# MIPI_To_HDMI.net
KiCad netlist of a schematic drawn in Altium Designer
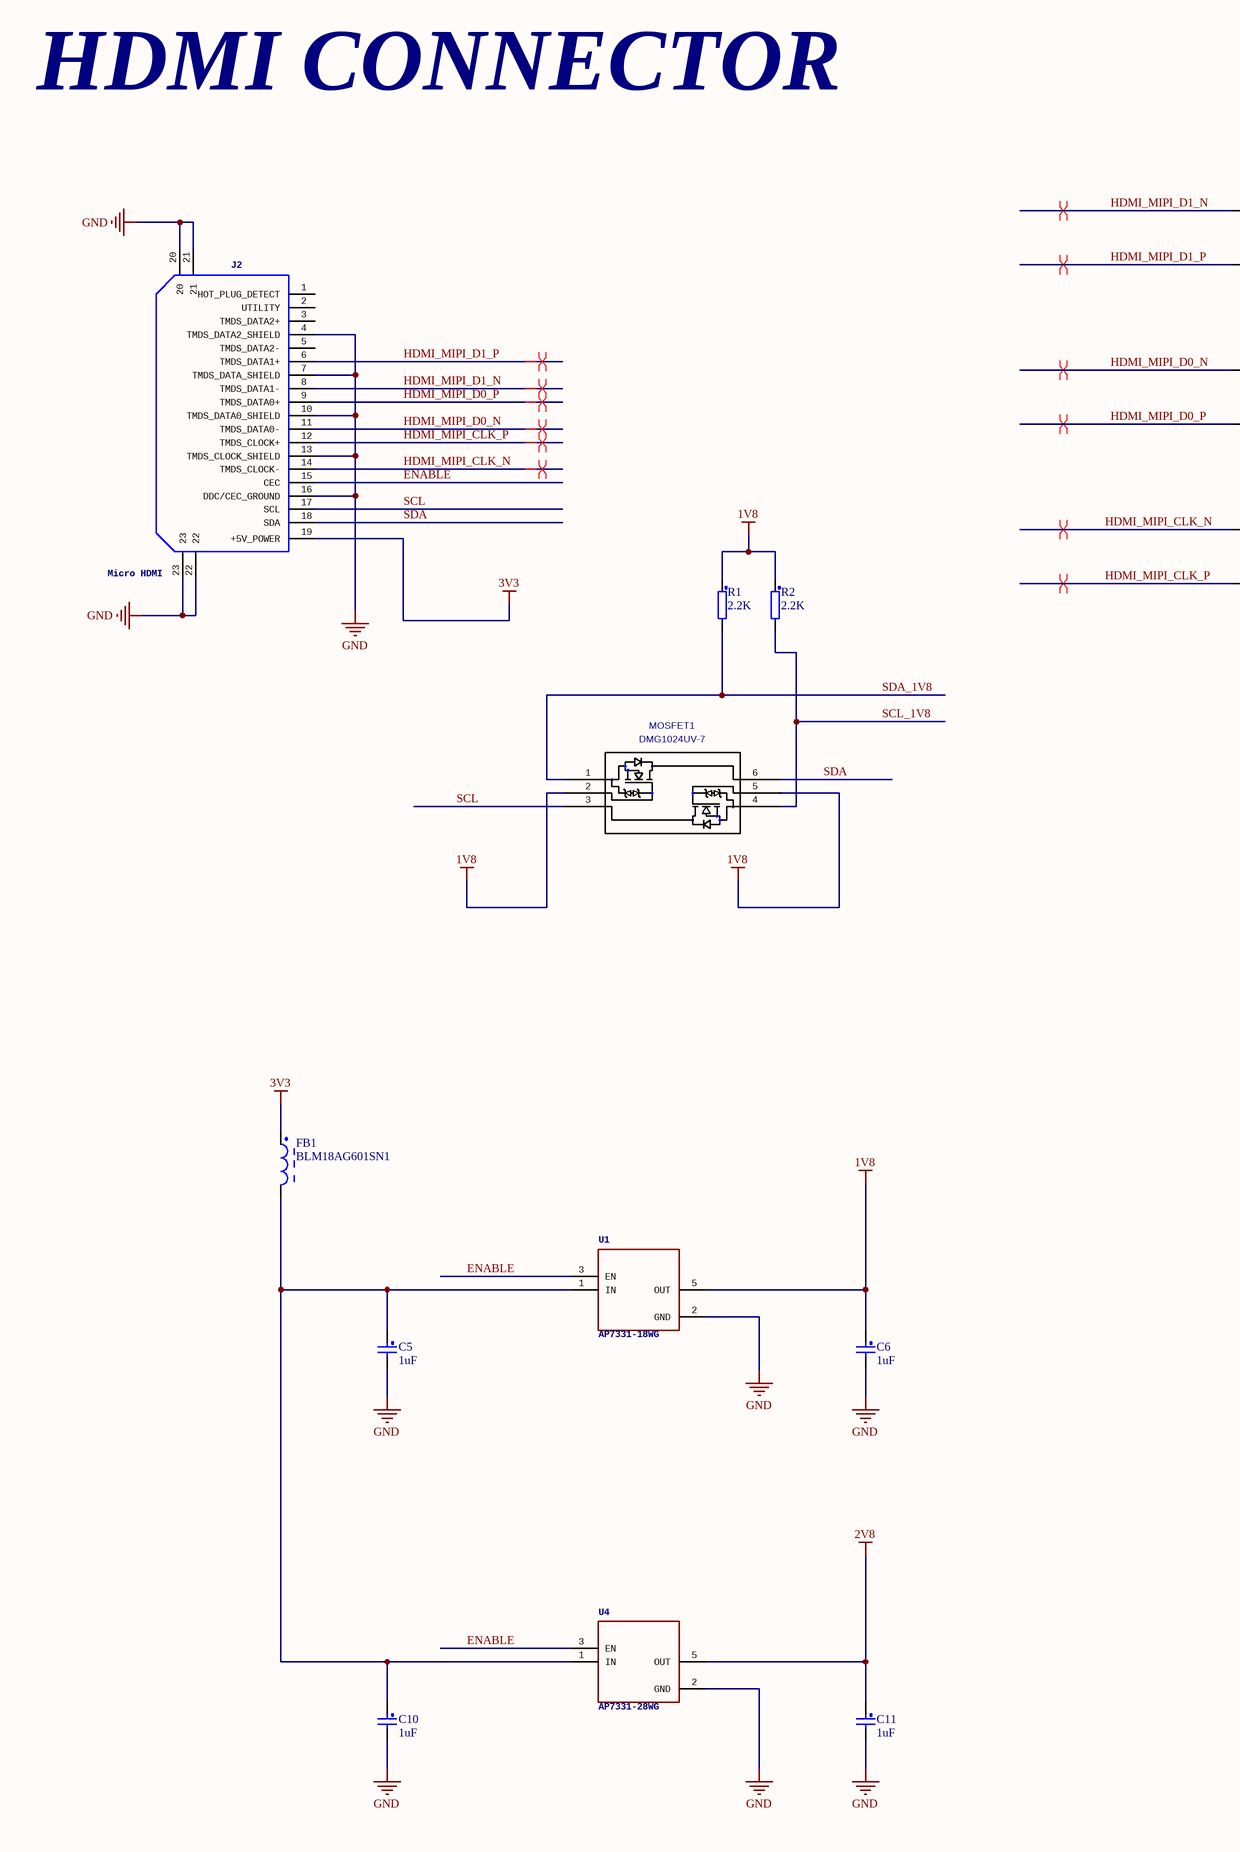
[diagram p0: MIPI_To_HDMI.SchDoc, left]
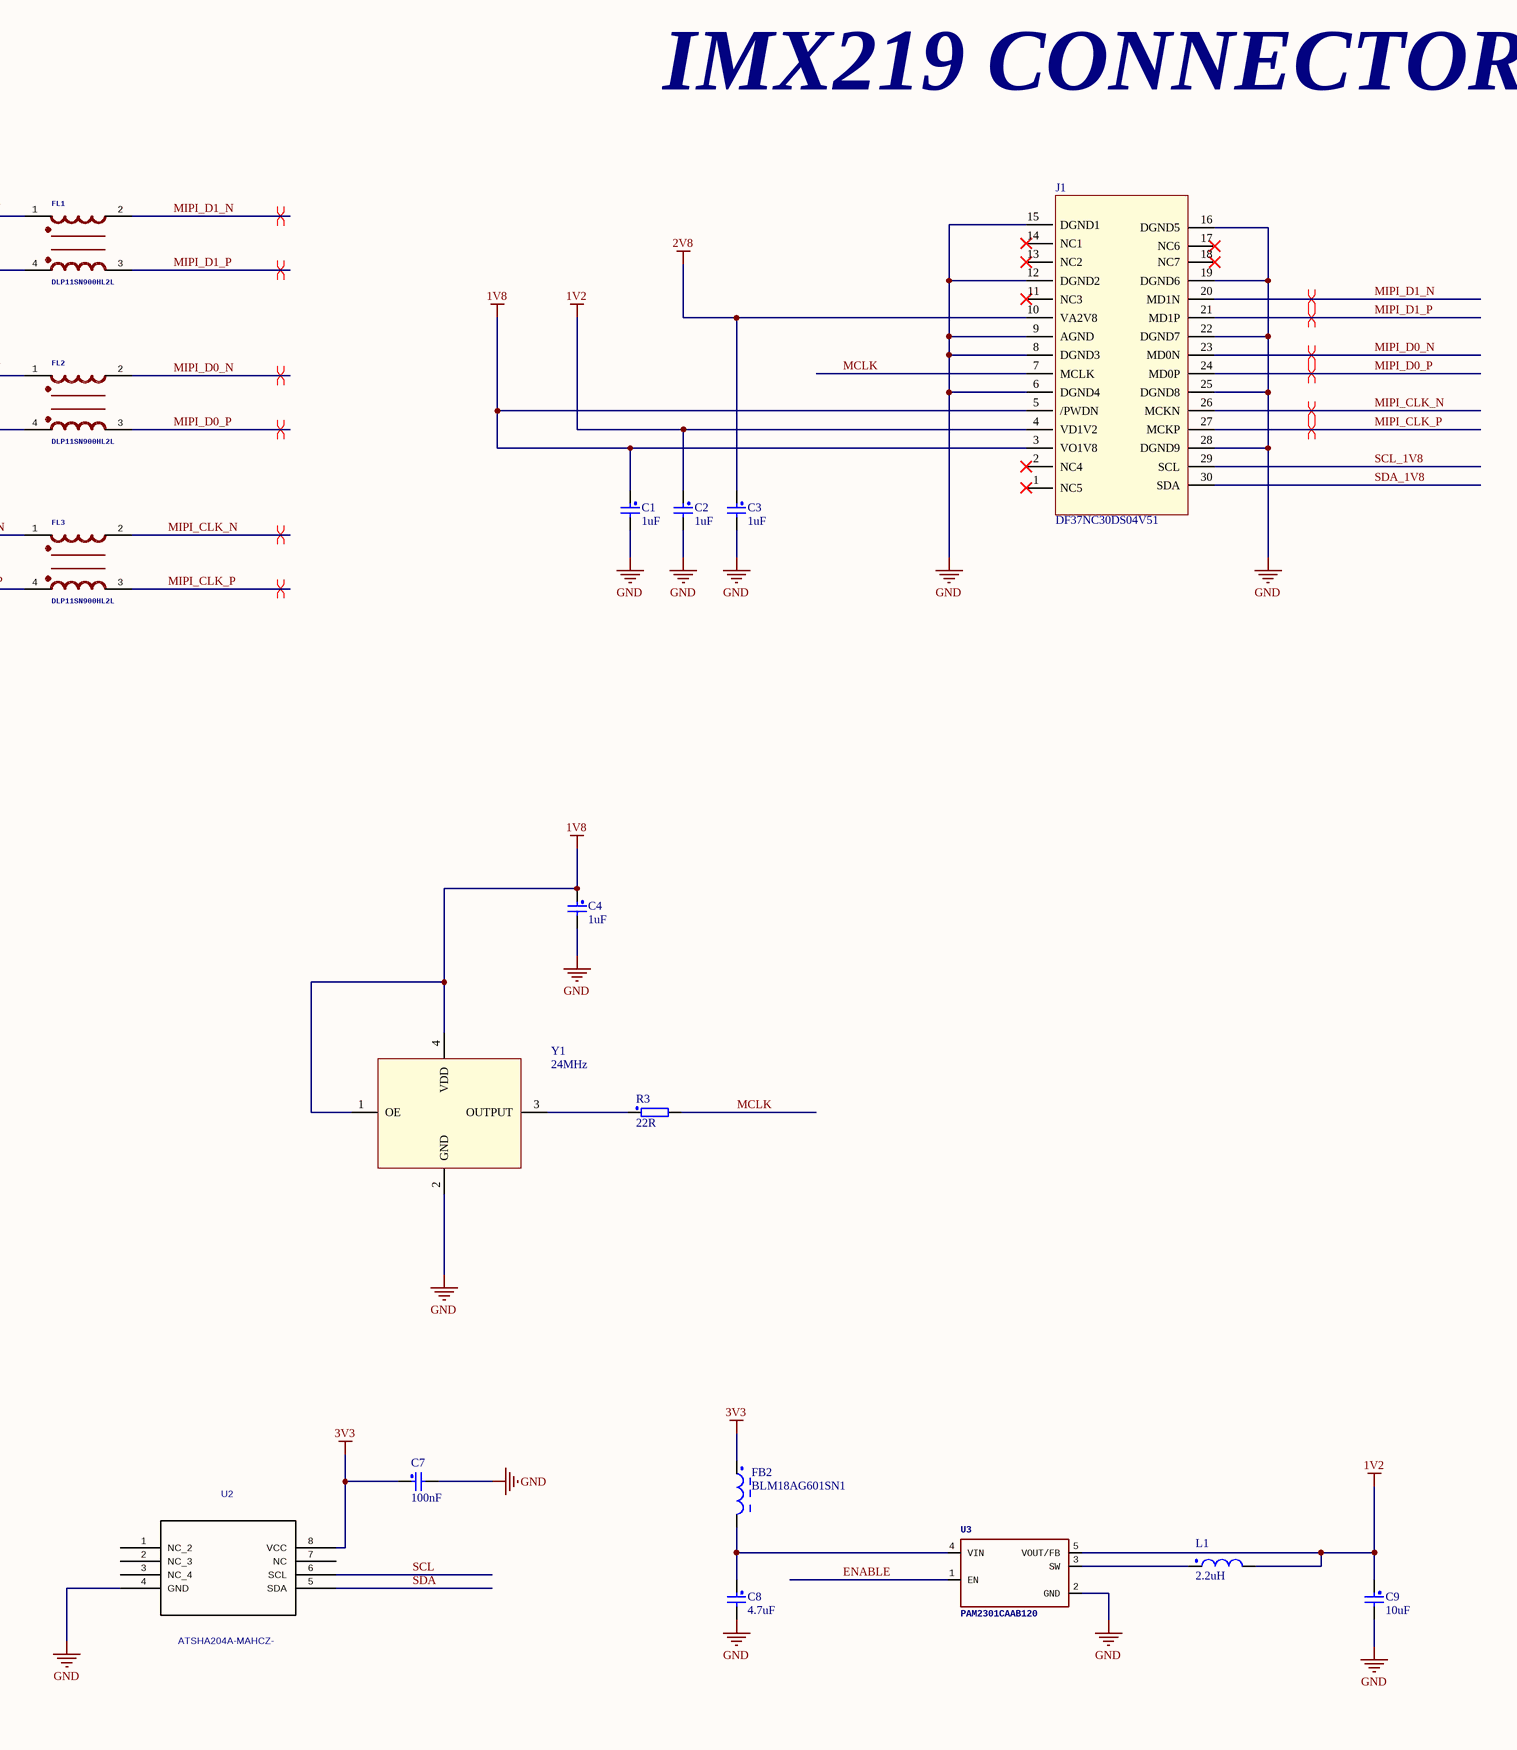
[diagram p1: MIPI_To_HDMI.SchDoc, right]

(export (version "E")
  (design (tool "Eeschema 10.0.6"))
  (components
    (comp (ref "C1")
      (value "1uF")
      (footprint "CAP-0402")
      (description "Capacitor")
      (libsource (lib "TASK-3DLIB") (part "CAP"))
    )
    (comp (ref "C2")
      (value "1uF")
      (footprint "CAP-0402")
      (description "Capacitor")
      (libsource (lib "TASK-3DLIB") (part "CAP"))
    )
    (comp (ref "C3")
      (value "1uF")
      (footprint "CAP-0402")
      (description "Capacitor")
      (libsource (lib "TASK-3DLIB") (part "CAP"))
    )
    (comp (ref "C4")
      (value "1uF")
      (footprint "CAP-0402")
      (description "Capacitor")
      (libsource (lib "TASK-3DLIB") (part "CAP"))
    )
    (comp (ref "C5")
      (value "1uF")
      (footprint "CAP-0402")
      (description "Capacitor")
      (libsource (lib "TASK-3DLIB") (part "CAP"))
    )
    (comp (ref "C6")
      (value "1uF")
      (footprint "CAP-0402")
      (description "Capacitor")
      (libsource (lib "TASK-3DLIB") (part "CAP"))
    )
    (comp (ref "C7")
      (value "100nF")
      (footprint "CAP-0402")
      (description "Capacitor")
      (libsource (lib "TASK-3DLIB") (part "CAP"))
    )
    (comp (ref "C8")
      (value "4.7uF")
      (footprint "CAP-0603")
      (description "Capacitor")
      (libsource (lib "TASK-3DLIB") (part "CAP"))
    )
    (comp (ref "C9")
      (value "10uF")
      (footprint "CAP-0805-S")
      (description "Capacitor")
      (libsource (lib "TASK-3DLIB") (part "CAP"))
    )
    (comp (ref "C10")
      (value "1uF")
      (footprint "CAP-0402")
      (description "Capacitor")
      (libsource (lib "TASK-3DLIB") (part "CAP"))
    )
    (comp (ref "C11")
      (value "1uF")
      (footprint "CAP-0402")
      (description "Capacitor")
      (libsource (lib "TASK-3DLIB") (part "CAP"))
    )
    (comp (ref "FB1")
      (value "BLM18AG601SN1")
      (footprint "FBD-0603-S")
      (description "Inductor")
      (libsource (lib "TASK-3DLIB") (part "INDUCTOR"))
    )
    (comp (ref "FB2")
      (value "BLM18AG601SN1")
      (footprint "FBD-0603-S")
      (description "Inductor")
      (libsource (lib "TASK-3DLIB") (part "INDUCTOR"))
    )
    (comp (ref "FL1")
      (value "DLP11SN900HL2L")
      (footprint "DLP11SN900HL2L")
      (fields (field (name "MF") "Murata") (field (name "DIGI-KEY_PART_NUMBER") "490-5143-1-ND"))
      (libsource (lib "TASK-3DLIB") (part "DLP11SN900HL2L"))
    )
    (comp (ref "FL2")
      (value "DLP11SN900HL2L")
      (footprint "DLP11SN900HL2L")
      (fields (field (name "MF") "Murata") (field (name "DIGI-KEY_PART_NUMBER") "490-5143-1-ND"))
      (libsource (lib "TASK-3DLIB") (part "DLP11SN900HL2L"))
    )
    (comp (ref "FL3")
      (value "DLP11SN900HL2L")
      (footprint "DLP11SN900HL2L")
      (fields (field (name "MF") "Murata") (field (name "DIGI-KEY_PART_NUMBER") "490-5143-1-ND"))
      (libsource (lib "TASK-3DLIB") (part "DLP11SN900HL2L"))
    )
    (comp (ref "J1")
      (value "DF37NC30DS04V51")
      (footprint "DF37NC30DS04V51")
      (libsource (lib "TASK-3DLIB") (part "DF37NC30DS04V51"))
    )
    (comp (ref "J2")
      (value "Micro HDMI")
      (footprint "HDMI-0467650301")
      (fields (field (name "MANUFACTURER_PART_NUMBER") "0467650301"))
      (libsource (lib "TASK-3DLIB") (part "HDMI-0467650301"))
    )
    (comp (ref "L1")
      (value "2.2uH")
      (footprint "IND-1008")
      (description "Inductor")
      (libsource (lib "TASK-3DLIB") (part "INDUCTOR"))
    )
    (comp (ref "MOSFET1")
      (value "DMG1024UV-7")
      (footprint "SOT-563_DIO")
      (fields (field (name "COPYRIGHT") "Copyright (C) 2018 Accelerated Designs. All rights reserved"))
      (libsource (lib "TASK-3DLIB") (part "DMG1024UV-7"))
    )
    (comp (ref "R1") (value "2.2K") (footprint "RES-0402") (libsource (lib "TASK-3DLIB") (part "RES")))
    (comp (ref "R2") (value "2.2K") (footprint "RES-0402") (libsource (lib "TASK-3DLIB") (part "RES")))
    (comp (ref "R3") (value "22R") (footprint "RES-0402") (libsource (lib "TASK-3DLIB") (part "RES")))
    (comp (ref "U1")
      (value "AP7331-18WG")
      (footprint "AP7331-sot-25")
      (fields
        (field (name "MP") "AP7331-18WG-7")
        (field (name "MF") "Diodes Inc.")
        (field (name "DIGI-KEY_PART_NUMBER") "AP7331-18WG-7DICT-ND")
      )
      (libsource (lib "TASK-3DLIB") (part "AP7331-xxWG-7"))
    )
    (comp (ref "U2")
      (value "ATSHA204A-MAHCZ-")
      (footprint "ATSHA204A")
      (fields
        (field (name "MANUFACTURER_PART_NUMBER") "ATSHA204A-MAHCZ-T")
        (field (name "COPYRIGHT") "Copyright (C) 2018 Accelerated Designs. All rights reserved")
      )
      (libsource (lib "TASK-3DLIB") (part "ATSHA204A-MAHCZ-"))
    )
    (comp (ref "U3")
      (value "PAM2301CAAB120")
      (footprint "PAM2301CAAB120")
      (fields (field (name "MF") "Diodes Inc.") (field (name "DIGI-KEY_PART_NUMBER") "PAM2301CAAB120DI-ND"))
      (libsource (lib "TASK-3DLIB") (part "PAM2301CAAB120"))
    )
    (comp (ref "U4")
      (value "AP7331-28WG")
      (footprint "AP7331-sot-25")
      (fields
        (field (name "MP") "AP7331-18WG-7")
        (field (name "MF") "Diodes Inc.")
        (field (name "DIGI-KEY_PART_NUMBER") "AP7331-18WG-7DICT-ND")
      )
      (libsource (lib "TASK-3DLIB") (part "AP7331-xxWG-7"))
    )
    (comp (ref "Y1") (value "24MHz") (footprint "3225-OSC") (libsource (lib "TASK-3DLIB") (part "OSC-3225")))
  )
  (nets
    (net (code "1") (name "/ENABLE") (class "Default")
      (node (ref "J2") (pin "15") (pinfunction "CEC_15") (pintype "passive"))
      (node (ref "U1") (pin "3") (pinfunction "EN_3") (pintype "passive"))
      (node (ref "U3") (pin "1") (pinfunction "EN_1") (pintype "passive"))
      (node (ref "U4") (pin "3") (pinfunction "EN_3") (pintype "passive"))
    )
    (net (code "2") (name "/HDMI_MIPI_CLK_N") (class "Default")
      (node (ref "FL3") (pin "1") (pinfunction "1_1") (pintype "passive"))
      (node (ref "J2") (pin "14") (pinfunction "TMDS_CLOCK-_14") (pintype "passive"))
    )
    (net (code "3") (name "/HDMI_MIPI_CLK_P") (class "Default")
      (node (ref "FL3") (pin "4") (pinfunction "4_4") (pintype "passive"))
      (node (ref "J2") (pin "12") (pinfunction "TMDS_CLOCK+_12") (pintype "passive"))
    )
    (net (code "4") (name "/HDMI_MIPI_D0_N") (class "Default")
      (node (ref "FL2") (pin "1") (pinfunction "1_1") (pintype "passive"))
      (node (ref "J2") (pin "11") (pinfunction "TMDS_DATA0-_11") (pintype "passive"))
    )
    (net (code "5") (name "/HDMI_MIPI_D0_P") (class "Default")
      (node (ref "FL2") (pin "4") (pinfunction "4_4") (pintype "passive"))
      (node (ref "J2") (pin "9") (pinfunction "TMDS_DATA0+_9") (pintype "passive"))
    )
    (net (code "6") (name "/HDMI_MIPI_D1_N") (class "Default")
      (node (ref "FL1") (pin "1") (pinfunction "1_1") (pintype "passive"))
      (node (ref "J2") (pin "8") (pinfunction "TMDS_DATA1-_8") (pintype "passive"))
    )
    (net (code "7") (name "/HDMI_MIPI_D1_P") (class "Default")
      (node (ref "FL1") (pin "4") (pinfunction "4_4") (pintype "passive"))
      (node (ref "J2") (pin "6") (pinfunction "TMDS_DATA1+_6") (pintype "passive"))
    )
    (net (code "8") (name "/MCLK") (class "Default")
      (node (ref "J1") (pin "7") (pinfunction "MCLK_7") (pintype "passive"))
      (node (ref "R3") (pin "2") (pintype "passive"))
    )
    (net (code "9") (name "/MIPI_CLK_N") (class "Default")
      (node (ref "FL3") (pin "2") (pinfunction "2_2") (pintype "passive"))
      (node (ref "J1") (pin "26") (pinfunction "MCKN_26") (pintype "passive"))
    )
    (net (code "10") (name "/MIPI_CLK_P") (class "Default")
      (node (ref "FL3") (pin "3") (pinfunction "3_3") (pintype "passive"))
      (node (ref "J1") (pin "27") (pinfunction "MCKP_27") (pintype "passive"))
    )
    (net (code "11") (name "/MIPI_D0_N") (class "Default")
      (node (ref "FL2") (pin "2") (pinfunction "2_2") (pintype "passive"))
      (node (ref "J1") (pin "23") (pinfunction "MD0N_23") (pintype "passive"))
    )
    (net (code "12") (name "/MIPI_D0_P") (class "Default")
      (node (ref "FL2") (pin "3") (pinfunction "3_3") (pintype "passive"))
      (node (ref "J1") (pin "24") (pinfunction "MD0P_24") (pintype "passive"))
    )
    (net (code "13") (name "/MIPI_D1_N") (class "Default")
      (node (ref "FL1") (pin "2") (pinfunction "2_2") (pintype "passive"))
      (node (ref "J1") (pin "20") (pinfunction "MD1N_20") (pintype "passive"))
    )
    (net (code "14") (name "/MIPI_D1_P") (class "Default")
      (node (ref "FL1") (pin "3") (pinfunction "3_3") (pintype "passive"))
      (node (ref "J1") (pin "21") (pinfunction "MD1P_21") (pintype "passive"))
    )
    (net (code "15") (name "/SCL") (class "Default")
      (node (ref "J2") (pin "17") (pinfunction "SCL_17") (pintype "passive"))
      (node (ref "MOSFET1") (pin "3") (pinfunction "D1_3") (pintype "passive"))
      (node (ref "U2") (pin "6") (pinfunction "SCL_6") (pintype "passive"))
    )
    (net (code "16") (name "/SCL_1V8") (class "Default")
      (node (ref "J1") (pin "29") (pinfunction "SCL_29") (pintype "passive"))
      (node (ref "MOSFET1") (pin "4") (pinfunction "S1_4") (pintype "passive"))
      (node (ref "R2") (pin "2") (pintype "passive"))
    )
    (net (code "17") (name "/SDA") (class "Default")
      (node (ref "J2") (pin "18") (pinfunction "SDA_18") (pintype "passive"))
      (node (ref "MOSFET1") (pin "6") (pinfunction "D2_6") (pintype "passive"))
      (node (ref "U2") (pin "5") (pinfunction "SDA_5") (pintype "passive"))
    )
    (net (code "18") (name "/SDA_1V8") (class "Default")
      (node (ref "J1") (pin "30") (pinfunction "SDA_30") (pintype "passive"))
      (node (ref "MOSFET1") (pin "1") (pinfunction "S2_1") (pintype "passive"))
      (node (ref "R1") (pin "2") (pintype "passive"))
    )
    (net (code "19") (name "1V2") (class "Default")
      (node (ref "C2") (pin "1") (pinfunction "1_1") (pintype "passive"))
      (node (ref "C9") (pin "1") (pinfunction "1_1") (pintype "passive"))
      (node (ref "J1") (pin "4") (pinfunction "VD1V2_4") (pintype "passive"))
      (node (ref "L1") (pin "2") (pinfunction "2_2") (pintype "passive"))
      (node (ref "U3") (pin "5") (pinfunction "VOUT/FB_5") (pintype "passive"))
    )
    (net (code "20") (name "1V8") (class "Default")
      (node (ref "C1") (pin "1") (pinfunction "1_1") (pintype "passive"))
      (node (ref "C4") (pin "1") (pinfunction "1_1") (pintype "passive"))
      (node (ref "C6") (pin "1") (pinfunction "1_1") (pintype "passive"))
      (node (ref "J1") (pin "3") (pinfunction "VO1V8_3") (pintype "passive"))
      (node (ref "J1") (pin "5") (pinfunction "/PWDN_5") (pintype "passive"))
      (node (ref "MOSFET1") (pin "2") (pinfunction "G2_2") (pintype "passive"))
      (node (ref "MOSFET1") (pin "5") (pinfunction "G1_5") (pintype "passive"))
      (node (ref "R1") (pin "1") (pintype "passive"))
      (node (ref "R2") (pin "1") (pintype "passive"))
      (node (ref "U1") (pin "5") (pinfunction "OUT_5") (pintype "passive"))
      (node (ref "Y1") (pin "1") (pinfunction "OE_1") (pintype "passive"))
      (node (ref "Y1") (pin "4") (pinfunction "VDD_4") (pintype "passive"))
    )
    (net (code "21") (name "2V8") (class "Default")
      (node (ref "C11") (pin "1") (pinfunction "1_1") (pintype "passive"))
      (node (ref "C3") (pin "1") (pinfunction "1_1") (pintype "passive"))
      (node (ref "J1") (pin "10") (pinfunction "VA2V8_10") (pintype "passive"))
      (node (ref "U4") (pin "5") (pinfunction "OUT_5") (pintype "passive"))
    )
    (net (code "22") (name "3V3") (class "Default")
      (node (ref "C7") (pin "1") (pinfunction "1_1") (pintype "passive"))
      (node (ref "FB1") (pin "1") (pinfunction "1_1") (pintype "passive"))
      (node (ref "FB2") (pin "1") (pinfunction "1_1") (pintype "passive"))
      (node (ref "J2") (pin "19") (pinfunction "+5V_POWER_19") (pintype "passive"))
      (node (ref "U2") (pin "8") (pinfunction "VCC_8") (pintype "power_in"))
    )
    (net (code "23") (name "GND") (class "Default")
      (node (ref "C1") (pin "2") (pinfunction "2_2") (pintype "passive"))
      (node (ref "C10") (pin "2") (pinfunction "2_2") (pintype "passive"))
      (node (ref "C11") (pin "2") (pinfunction "2_2") (pintype "passive"))
      (node (ref "C2") (pin "2") (pinfunction "2_2") (pintype "passive"))
      (node (ref "C3") (pin "2") (pinfunction "2_2") (pintype "passive"))
      (node (ref "C4") (pin "2") (pinfunction "2_2") (pintype "passive"))
      (node (ref "C5") (pin "2") (pinfunction "2_2") (pintype "passive"))
      (node (ref "C6") (pin "2") (pinfunction "2_2") (pintype "passive"))
      (node (ref "C7") (pin "2") (pinfunction "2_2") (pintype "passive"))
      (node (ref "C8") (pin "2") (pinfunction "2_2") (pintype "passive"))
      (node (ref "C9") (pin "2") (pinfunction "2_2") (pintype "passive"))
      (node (ref "J1") (pin "12") (pinfunction "DGND2_12") (pintype "passive"))
      (node (ref "J1") (pin "15") (pinfunction "DGND1_15") (pintype "passive"))
      (node (ref "J1") (pin "16") (pinfunction "DGND5_16") (pintype "passive"))
      (node (ref "J1") (pin "19") (pinfunction "DGND6_19") (pintype "passive"))
      (node (ref "J1") (pin "22") (pinfunction "DGND7_22") (pintype "passive"))
      (node (ref "J1") (pin "25") (pinfunction "DGND8_25") (pintype "passive"))
      (node (ref "J1") (pin "28") (pinfunction "DGND9_28") (pintype "passive"))
      (node (ref "J1") (pin "6") (pinfunction "DGND4_6") (pintype "passive"))
      (node (ref "J1") (pin "8") (pinfunction "DGND3_8") (pintype "passive"))
      (node (ref "J1") (pin "9") (pinfunction "AGND_9") (pintype "passive"))
      (node (ref "J2") (pin "10") (pinfunction "TMDS_DATA0_SHIELD_10") (pintype "passive"))
      (node (ref "J2") (pin "13") (pinfunction "TMDS_CLOCK_SHIELD_13") (pintype "passive"))
      (node (ref "J2") (pin "16") (pinfunction "DDC/CEC_GROUND_16") (pintype "passive"))
      (node (ref "J2") (pin "20") (pinfunction "20_20") (pintype "passive"))
      (node (ref "J2") (pin "21") (pinfunction "21_21") (pintype "passive"))
      (node (ref "J2") (pin "22") (pinfunction "22_22") (pintype "passive"))
      (node (ref "J2") (pin "23") (pinfunction "23_23") (pintype "passive"))
      (node (ref "J2") (pin "4") (pinfunction "TMDS_DATA2_SHIELD_4") (pintype "passive"))
      (node (ref "J2") (pin "7") (pinfunction "TMDS_DATA_SHIELD_7") (pintype "passive"))
      (node (ref "U1") (pin "2") (pinfunction "GND_2") (pintype "power_in"))
      (node (ref "U2") (pin "4") (pinfunction "GND_4") (pintype "power_in"))
      (node (ref "U3") (pin "2") (pinfunction "GND_2") (pintype "power_in"))
      (node (ref "U4") (pin "2") (pinfunction "GND_2") (pintype "power_in"))
      (node (ref "Y1") (pin "2") (pinfunction "GND_2") (pintype "passive"))
    )
    (net (code "24") (name "Net-(U1-IN)") (class "Default")
      (node (ref "C10") (pin "1") (pinfunction "1_1") (pintype "passive"))
      (node (ref "C5") (pin "1") (pinfunction "1_1") (pintype "passive"))
      (node (ref "FB1") (pin "2") (pinfunction "2_2") (pintype "passive"))
      (node (ref "U1") (pin "1") (pinfunction "IN_1") (pintype "passive"))
      (node (ref "U4") (pin "1") (pinfunction "IN_1") (pintype "passive"))
    )
    (net (code "25") (name "Net-(U3-SW)") (class "Default")
      (node (ref "L1") (pin "1") (pinfunction "1_1") (pintype "passive"))
      (node (ref "U3") (pin "3") (pinfunction "SW_3") (pintype "passive"))
    )
    (net (code "26") (name "Net-(U3-VIN)") (class "Default")
      (node (ref "C8") (pin "1") (pinfunction "1_1") (pintype "passive"))
      (node (ref "FB2") (pin "2") (pinfunction "2_2") (pintype "passive"))
      (node (ref "U3") (pin "4") (pinfunction "VIN_4") (pintype "passive"))
    )
    (net (code "27") (name "Net-(Y1-OUTPUT)") (class "Default")
      (node (ref "R3") (pin "1") (pintype "passive"))
      (node (ref "Y1") (pin "3") (pinfunction "OUTPUT_3") (pintype "passive"))
    )
    (net (code "28") (name "unconnected-(J1-NC1-Pad14)") (class "Default")
      (node (ref "J1") (pin "14") (pinfunction "NC1_14") (pintype "passive+no_connect"))
    )
    (net (code "29") (name "unconnected-(J1-NC2-Pad13)") (class "Default")
      (node (ref "J1") (pin "13") (pinfunction "NC2_13") (pintype "passive+no_connect"))
    )
    (net (code "30") (name "unconnected-(J1-NC3-Pad11)") (class "Default")
      (node (ref "J1") (pin "11") (pinfunction "NC3_11") (pintype "passive+no_connect"))
    )
    (net (code "31") (name "unconnected-(J1-NC4-Pad2)") (class "Default")
      (node (ref "J1") (pin "2") (pinfunction "NC4_2") (pintype "passive+no_connect"))
    )
    (net (code "32") (name "unconnected-(J1-NC5-Pad1)") (class "Default")
      (node (ref "J1") (pin "1") (pinfunction "NC5_1") (pintype "passive+no_connect"))
    )
    (net (code "33") (name "unconnected-(J1-NC6-Pad17)") (class "Default")
      (node (ref "J1") (pin "17") (pinfunction "NC6_17") (pintype "passive+no_connect"))
    )
    (net (code "34") (name "unconnected-(J1-NC7-Pad18)") (class "Default")
      (node (ref "J1") (pin "18") (pinfunction "NC7_18") (pintype "passive+no_connect"))
    )
    (net (code "35") (name "unconnected-(J2-HOT_PLUG_DETECT-Pad1)") (class "Default")
      (node (ref "J2") (pin "1") (pinfunction "HOT_PLUG_DETECT_1") (pintype "passive"))
    )
    (net (code "36") (name "unconnected-(J2-TMDS_DATA2+-Pad3)") (class "Default")
      (node (ref "J2") (pin "3") (pinfunction "TMDS_DATA2+_3") (pintype "passive"))
    )
    (net (code "37") (name "unconnected-(J2-TMDS_DATA2--Pad5)") (class "Default")
      (node (ref "J2") (pin "5") (pinfunction "TMDS_DATA2-_5") (pintype "passive"))
    )
    (net (code "38") (name "unconnected-(J2-UTILITY-Pad2)") (class "Default")
      (node (ref "J2") (pin "2") (pinfunction "UTILITY_2") (pintype "passive"))
    )
    (net (code "39") (name "unconnected-(U2-NC-Pad7)") (class "Default")
      (node (ref "U2") (pin "7") (pinfunction "NC_7") (pintype "passive"))
    )
    (net (code "40") (name "unconnected-(U2-NC_2-Pad1)") (class "Default")
      (node (ref "U2") (pin "1") (pinfunction "NC_2_1") (pintype "passive"))
    )
    (net (code "41") (name "unconnected-(U2-NC_3-Pad2)") (class "Default")
      (node (ref "U2") (pin "2") (pinfunction "NC_3_2") (pintype "passive"))
    )
    (net (code "42") (name "unconnected-(U2-NC_4-Pad3)") (class "Default")
      (node (ref "U2") (pin "3") (pinfunction "NC_4_3") (pintype "passive"))
    )
  )
)
